# uC.net
KiCad netlist of a schematic drawn in Altium Designer
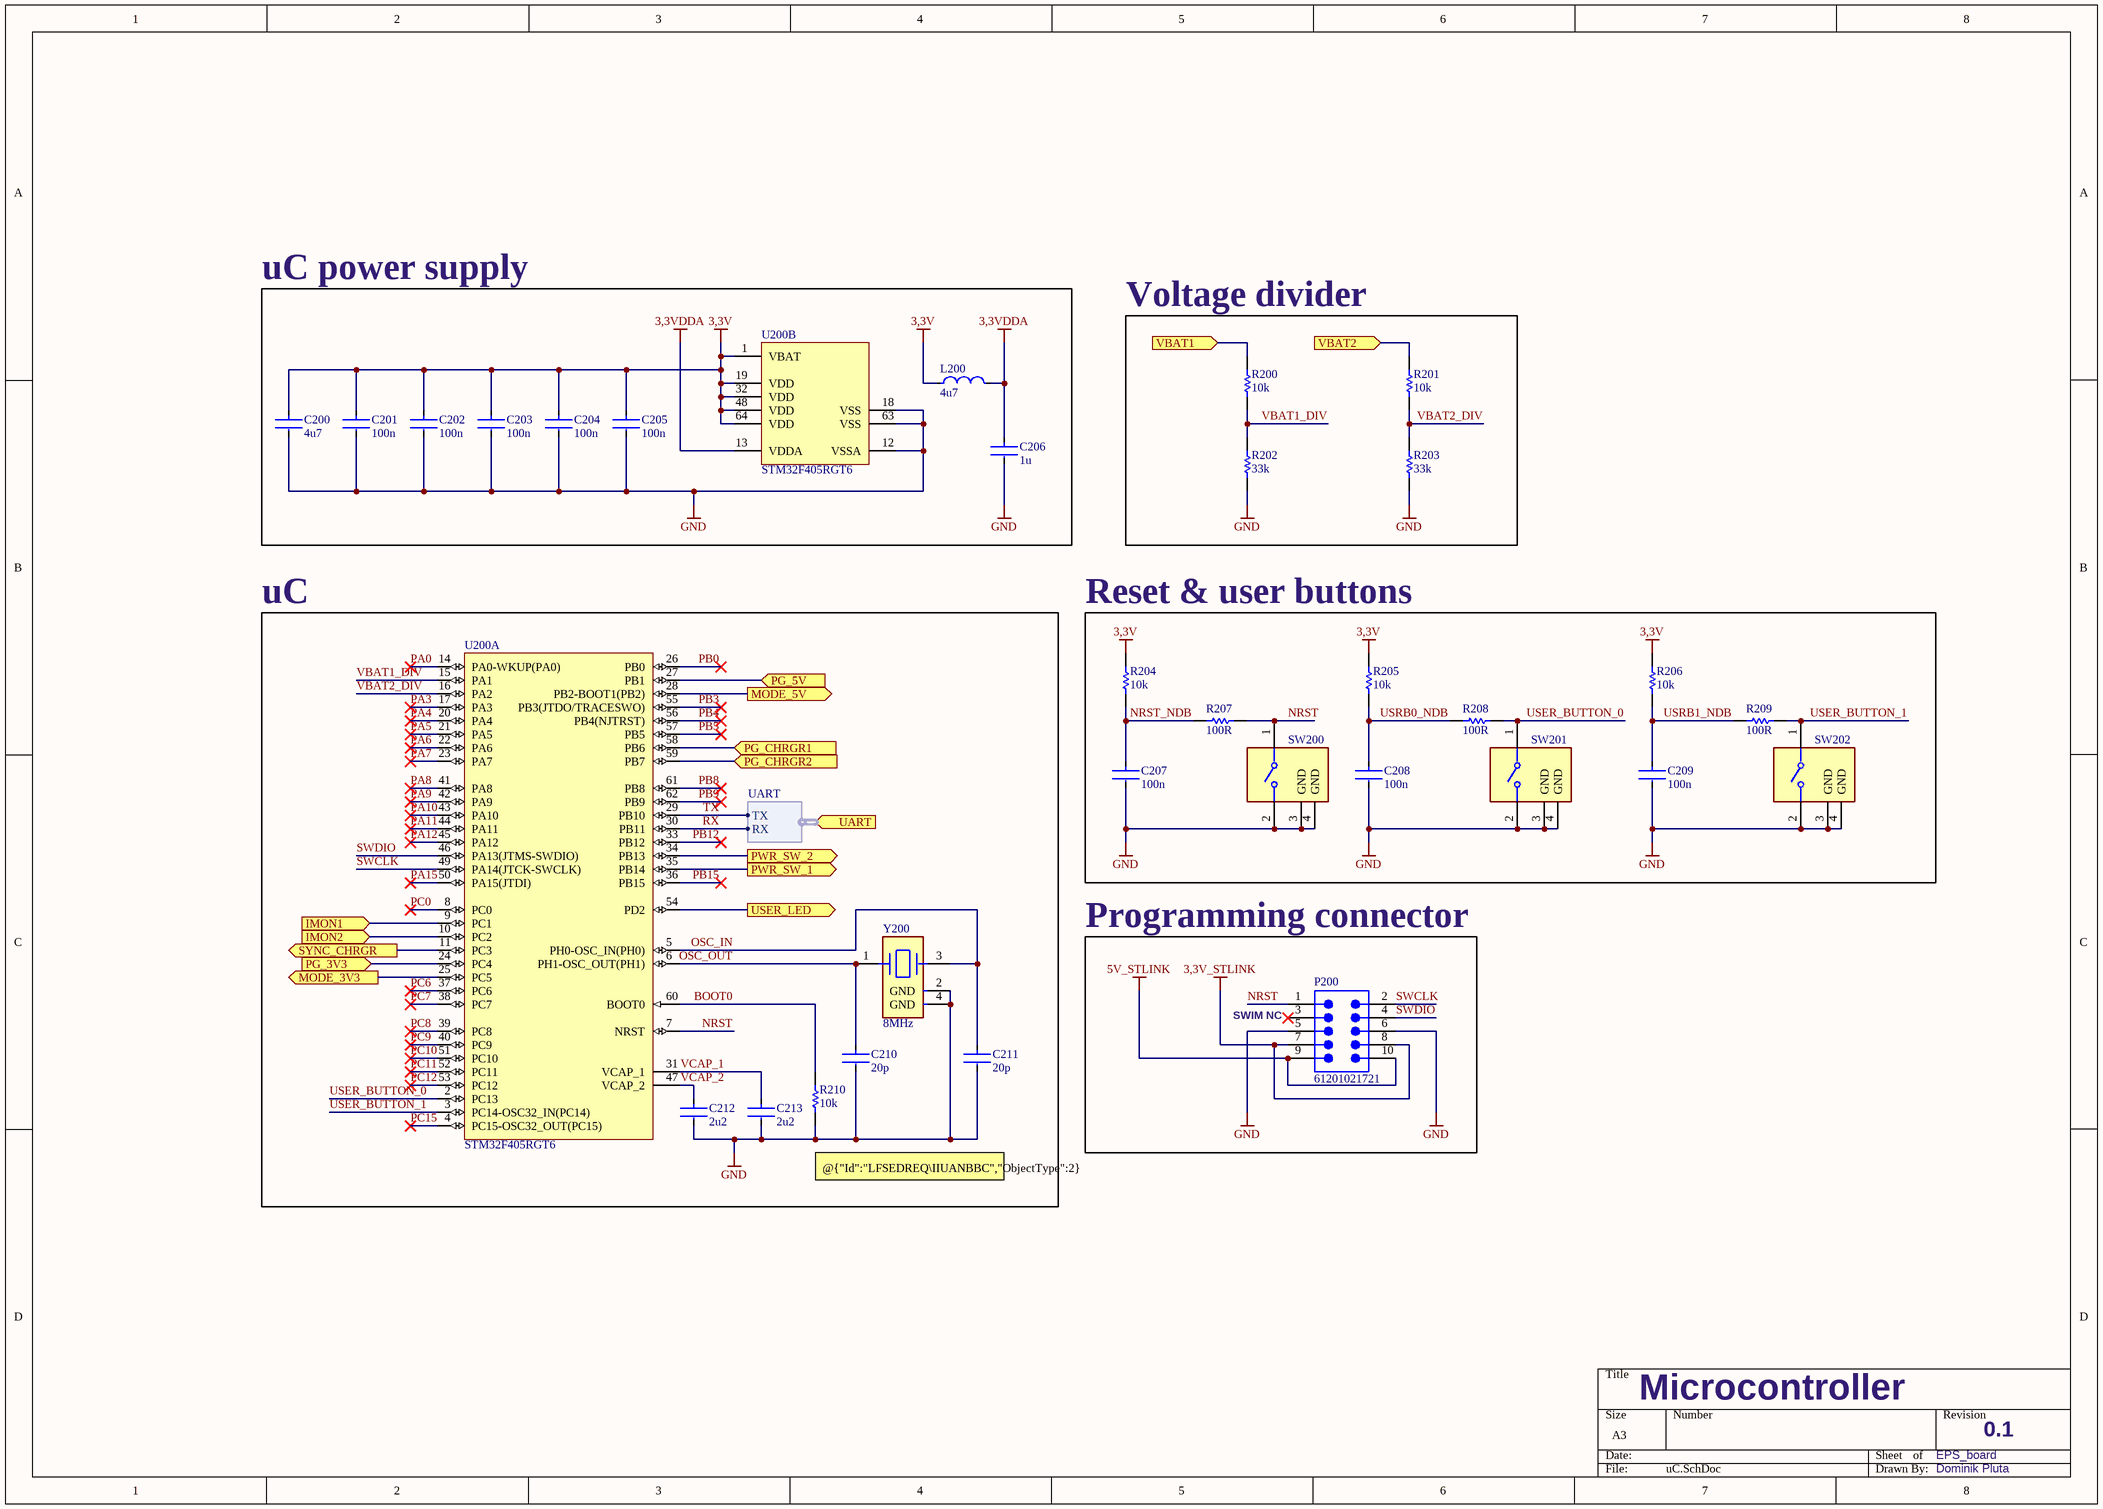
[diagram p0: uC.SchDoc]

(export (version "E")
  (design (tool "Eeschema 10.0.6"))
  (components
    (comp (ref "C200")
      (value "4u7")
      (footprint "FP-C0603C-CF-MFG")
      (description "CAP CER 0.1UF 50V X7R 0603")
      (fields (field (name "TOLERANCE") "0.1") (field (name "MANUFACTURER") "KEMET"))
      (libsource (lib "Altium Content Vault") (part "b4654b650e69147ec39a6b967a45e02"))
    )
    (comp (ref "C201")
      (value "100n")
      (footprint "FP-C0603C-CF-MFG")
      (description "CAP 0.1 μF, X5R or X7R ceramic")
      (fields (field (name "TOLERANCE") "10"))
      (libsource (lib "Altium Content Vault") (part "b4654b650e69147ec39a6b967a45e02"))
    )
    (comp (ref "C202")
      (value "100n")
      (footprint "FP-C0603C-CF-MFG")
      (description "CAP 0.1 μF, X5R or X7R ceramic")
      (fields (field (name "TOLERANCE") "10"))
      (libsource (lib "Altium Content Vault") (part "b4654b650e69147ec39a6b967a45e02"))
    )
    (comp (ref "C203")
      (value "100n")
      (footprint "FP-C0603C-CF-MFG")
      (description "CAP 0.1 μF, X5R or X7R ceramic")
      (fields (field (name "TOLERANCE") "10"))
      (libsource (lib "Altium Content Vault") (part "b4654b650e69147ec39a6b967a45e02"))
    )
    (comp (ref "C204")
      (value "100n")
      (footprint "FP-C0603C-CF-MFG")
      (description "CAP 0.1 μF, X5R or X7R ceramic")
      (fields (field (name "TOLERANCE") "10"))
      (libsource (lib "Altium Content Vault") (part "b4654b650e69147ec39a6b967a45e02"))
    )
    (comp (ref "C205")
      (value "100n")
      (footprint "FP-C0603C-CF-MFG")
      (description "CAP 0.1 μF, X5R or X7R ceramic")
      (fields (field (name "TOLERANCE") "10"))
      (libsource (lib "Altium Content Vault") (part "b4654b650e69147ec39a6b967a45e02"))
    )
    (comp (ref "C206")
      (value "1u")
      (footprint "FP-C0603C-CF-MFG")
      (description "CAP CER 0.1UF 50V X7R 0603")
      (fields (field (name "TOLERANCE") "0.1") (field (name "MANUFACTURER") "KEMET"))
      (libsource (lib "Altium Content Vault") (part "b4654b650e69147ec39a6b967a45e02"))
    )
    (comp (ref "C207")
      (value "100n")
      (footprint "FP-C0603C-CF-MFG")
      (description "CAP 0.1 μF, ceramic")
      (fields (field (name "TOLERANCE") "10"))
      (libsource (lib "Altium Content Vault") (part "b4654b650e69147ec39a6b967a45e02"))
    )
    (comp (ref "C208")
      (value "100n")
      (footprint "FP-C0603C-CF-MFG")
      (description "CAP 0.1 μF, ceramic")
      (fields (field (name "TOLERANCE") "10"))
      (libsource (lib "Altium Content Vault") (part "b4654b650e69147ec39a6b967a45e02"))
    )
    (comp (ref "C209")
      (value "100n")
      (footprint "FP-C0603C-CF-MFG")
      (description "CAP 0.1 μF, ceramic")
      (fields (field (name "TOLERANCE") "10"))
      (libsource (lib "Altium Content Vault") (part "b4654b650e69147ec39a6b967a45e02"))
    )
    (comp (ref "C210")
      (value "20p")
      (footprint "FP-C0603C-CF-MFG")
      (description "CAP CER 50V X7R 0603")
      (fields (field (name "TOLERANCE") "0.1") (field (name "MANUFACTURER") "KEMET"))
      (libsource (lib "Altium Content Vault") (part "b4654b650e69147ec39a6b967a45e02"))
    )
    (comp (ref "C211")
      (value "20p")
      (footprint "FP-C0603C-CF-MFG")
      (description "CAP CER 50V X7R 0603")
      (fields (field (name "TOLERANCE") "0.1") (field (name "MANUFACTURER") "KEMET"))
      (libsource (lib "Altium Content Vault") (part "b4654b650e69147ec39a6b967a45e02"))
    )
    (comp (ref "C212")
      (value "2u2")
      (footprint "FP-C0603C-CF-MFG")
      (description "CAP CER 50V X7R 0603")
      (fields (field (name "TOLERANCE") "0.1") (field (name "MANUFACTURER") "KEMET"))
      (libsource (lib "Altium Content Vault") (part "b4654b650e69147ec39a6b967a45e02"))
    )
    (comp (ref "C213")
      (value "2u2")
      (footprint "FP-C0603C-CF-MFG")
      (description "CAP CER 50V X7R 0603")
      (fields (field (name "TOLERANCE") "0.1") (field (name "MANUFACTURER") "KEMET"))
      (libsource (lib "Altium Content Vault") (part "b4654b650e69147ec39a6b967a45e02"))
    )
    (comp (ref "L200")
      (value "4u7")
      (footprint "FP-LQM21DN_00-MFG")
      (description "Multilayer Type Inductor for General Circuits, 0805 (2012), 0.22μH, 10%, 0.38Ω, 250mA")
      (fields (field (name "TOLERANCE") "10%"))
      (libsource (lib "Altium Content Vault") (part "725321dda6339637d4d059423bc1c3c"))
    )
    (comp (ref "P200")
      (value "61201021721")
      (footprint "61201021721")
      (libsource (lib "Altium Content Vault") (part "Header_Male_2R_10P"))
    )
    (comp (ref "R200")
      (value "10k")
      (footprint "RESC0603(1608)_N")
      (description "10k 0.1W 5% 0603 SMD")
      (fields (field (name "TOLERANCE") "5 %") (field (name "POWER") "0.1 W"))
      (libsource (lib "Altium Content Vault") (part "RES"))
    )
    (comp (ref "R201")
      (value "10k")
      (footprint "RESC0603(1608)_N")
      (description "10k 0.1W 5% 0603  SMD")
      (fields (field (name "TOLERANCE") "5 %") (field (name "POWER") "0.1 W"))
      (libsource (lib "Altium Content Vault") (part "RES"))
    )
    (comp (ref "R202")
      (value "33k")
      (footprint "RESC0603(1608)_N")
      (description "33k 0.1W 5% 0603 SMD")
      (fields (field (name "TOLERANCE") "5 %") (field (name "POWER") "0.1 W"))
      (libsource (lib "Altium Content Vault") (part "RES"))
    )
    (comp (ref "R203")
      (value "33k")
      (footprint "RESC0603(1608)_N")
      (description "33k 0.1W 5% 0603 SMD")
      (fields (field (name "TOLERANCE") "5 %") (field (name "POWER") "0.1 W"))
      (libsource (lib "Altium Content Vault") (part "RES"))
    )
    (comp (ref "R204")
      (value "10k")
      (footprint "RESC0603(1608)_N")
      (description "10k 0.1W 5% 0603 SMD")
      (fields (field (name "TOLERANCE") "5 %") (field (name "POWER") "0.1 W"))
      (libsource (lib "Altium Content Vault") (part "RES"))
    )
    (comp (ref "R205")
      (value "10k")
      (footprint "RESC0603(1608)_N")
      (description "10k 0.1W 5% 0603 SMD")
      (fields (field (name "TOLERANCE") "5 %") (field (name "POWER") "0.1 W"))
      (libsource (lib "Altium Content Vault") (part "RES"))
    )
    (comp (ref "R206")
      (value "10k")
      (footprint "RESC0603(1608)_N")
      (description "10k 0.1W 5% 0603 SMD")
      (fields (field (name "TOLERANCE") "5 %") (field (name "POWER") "0.1 W"))
      (libsource (lib "Altium Content Vault") (part "RES"))
    )
    (comp (ref "R207")
      (value "100R")
      (footprint "RESC0603(1608)_N")
      (description "100R 0.1W 5% 0603  SMD")
      (fields (field (name "TOLERANCE") "5 %") (field (name "POWER") "0.1 W"))
      (libsource (lib "Altium Content Vault") (part "RES"))
    )
    (comp (ref "R208")
      (value "100R")
      (footprint "RESC0603(1608)_N")
      (description "100R 0.1W 5% 0603  SMD")
      (fields (field (name "TOLERANCE") "5 %") (field (name "POWER") "0.1 W"))
      (libsource (lib "Altium Content Vault") (part "RES"))
    )
    (comp (ref "R209")
      (value "100R")
      (footprint "RESC0603(1608)_N")
      (description "100R 0.1W 5% 0603  SMD")
      (fields (field (name "TOLERANCE") "5 %") (field (name "POWER") "0.1 W"))
      (libsource (lib "Altium Content Vault") (part "RES"))
    )
    (comp (ref "R210")
      (value "10k")
      (footprint "RESC0603(1608)_N")
      (description "10k 0.1W 5% 0603 SMD")
      (fields (field (name "TOLERANCE") "5 %") (field (name "POWER") "0.1 W"))
      (libsource (lib "Altium Content Vault") (part "RES"))
    )
    (comp (ref "SW200")
      (value "B3F-3122")
      (footprint "FP-B3F-3122-MFG")
      (description "SWITCH TACTILE SPST-NO 0.05A 24V")
      (libsource (lib "Altium Content Vault") (part "05c531d4b500f7e9514fa3f65f375ae"))
    )
    (comp (ref "SW201")
      (value "B3F-3122")
      (footprint "FP-B3F-3122-MFG")
      (description "SWITCH TACTILE SPST-NO 0.05A 24V")
      (libsource (lib "Altium Content Vault") (part "05c531d4b500f7e9514fa3f65f375ae"))
    )
    (comp (ref "SW202")
      (value "B3F-3122")
      (footprint "FP-B3F-3122-MFG")
      (description "SWITCH TACTILE SPST-NO 0.05A 24V")
      (libsource (lib "Altium Content Vault") (part "05c531d4b500f7e9514fa3f65f375ae"))
    )
    (comp (ref "U200")
      (value "STM32F405RGT6")
      (footprint "STM-LQFP64_M")
      (fields (field (name "MANUFACTURER") "STMicroelectronics"))
      (libsource (lib "Altium Content Vault") (part "MC-ARM-STM32F4X5-SQ64"))
    )
    (comp (ref "Y200")
      (value "8MHz")
      (footprint "FP-7M-MFG")
      (description "Crystal oscillator 8MHz")
      (fields (field (name "TOLERANCE") "10ppm"))
      (libsource (lib "Altium Content Vault") (part "41079aabb0e87794b56622915be14ed"))
    )
  )
  (nets
    (net (code "3") (name "/BOOT0") (class "Default")
      (node (ref "R210") (pin "2") (pinfunction "2_2") (pintype "passive"))
      (node (ref "U200") (pin "60") (pinfunction "BOOT0_60") (pintype "input"))
    )
    (net (code "4") (name "/IMON1") (class "Default")
      (node (ref "U200") (pin "9") (pinfunction "PC1_9") (pintype "bidirectional"))
    )
    (net (code "5") (name "/IMON2") (class "Default")
      (node (ref "U200") (pin "10") (pinfunction "PC2_10") (pintype "bidirectional"))
    )
    (net (code "6") (name "/MODE_3V3") (class "Default")
      (node (ref "U200") (pin "25") (pinfunction "PC5_25") (pintype "bidirectional"))
    )
    (net (code "7") (name "/MODE_5V") (class "Default")
      (node (ref "U200") (pin "28") (pinfunction "PB2-BOOT1(PB2)_28") (pintype "bidirectional"))
    )
    (net (code "8") (name "/NRST") (class "Default")
      (node (ref "P200") (pin "1") (pinfunction "1_1") (pintype "passive"))
      (node (ref "R207") (pin "1") (pinfunction "1_1") (pintype "passive"))
      (node (ref "SW200") (pin "1") (pinfunction "1_1") (pintype "passive"))
      (node (ref "U200") (pin "7") (pinfunction "NRST_7") (pintype "bidirectional"))
    )
    (net (code "9") (name "/NRST_NDB") (class "Default")
      (node (ref "C207") (pin "1") (pinfunction "1_1") (pintype "passive"))
      (node (ref "R204") (pin "1") (pinfunction "1_1") (pintype "passive"))
      (node (ref "R207") (pin "2") (pinfunction "2_2") (pintype "passive"))
    )
    (net (code "10") (name "/OSC_IN") (class "Default")
      (node (ref "C211") (pin "1") (pinfunction "1_1") (pintype "passive"))
      (node (ref "U200") (pin "5") (pinfunction "PH0-OSC_IN(PH0)_5") (pintype "bidirectional"))
      (node (ref "Y200") (pin "3") (pinfunction "3_3") (pintype "passive"))
    )
    (net (code "11") (name "/OSC_OUT") (class "Default")
      (node (ref "C210") (pin "1") (pinfunction "1_1") (pintype "passive"))
      (node (ref "U200") (pin "6") (pinfunction "PH1-OSC_OUT(PH1)_6") (pintype "bidirectional"))
      (node (ref "Y200") (pin "1") (pinfunction "1_1") (pintype "passive"))
    )
    (net (code "12") (name "/PA0") (class "Default")
      (node (ref "U200") (pin "14") (pinfunction "PA0-WKUP(PA0)_14") (pintype "bidirectional+no_connect"))
    )
    (net (code "13") (name "/PA3") (class "Default")
      (node (ref "U200") (pin "17") (pinfunction "PA3_17") (pintype "bidirectional+no_connect"))
    )
    (net (code "14") (name "/PA4") (class "Default")
      (node (ref "U200") (pin "20") (pinfunction "PA4_20") (pintype "bidirectional+no_connect"))
    )
    (net (code "15") (name "/PA5") (class "Default")
      (node (ref "U200") (pin "21") (pinfunction "PA5_21") (pintype "bidirectional+no_connect"))
    )
    (net (code "16") (name "/PA6") (class "Default")
      (node (ref "U200") (pin "22") (pinfunction "PA6_22") (pintype "bidirectional+no_connect"))
    )
    (net (code "17") (name "/PA7") (class "Default")
      (node (ref "U200") (pin "23") (pinfunction "PA7_23") (pintype "bidirectional+no_connect"))
    )
    (net (code "18") (name "/PA8") (class "Default")
      (node (ref "U200") (pin "41") (pinfunction "PA8_41") (pintype "bidirectional+no_connect"))
    )
    (net (code "19") (name "/PA9") (class "Default")
      (node (ref "U200") (pin "42") (pinfunction "PA9_42") (pintype "bidirectional+no_connect"))
    )
    (net (code "20") (name "/PA10") (class "Default")
      (node (ref "U200") (pin "43") (pinfunction "PA10_43") (pintype "bidirectional+no_connect"))
    )
    (net (code "21") (name "/PA11") (class "Default")
      (node (ref "U200") (pin "44") (pinfunction "PA11_44") (pintype "bidirectional+no_connect"))
    )
    (net (code "22") (name "/PA12") (class "Default")
      (node (ref "U200") (pin "45") (pinfunction "PA12_45") (pintype "bidirectional+no_connect"))
    )
    (net (code "23") (name "/PA15") (class "Default")
      (node (ref "U200") (pin "50") (pinfunction "PA15(JTDI)_50") (pintype "bidirectional+no_connect"))
    )
    (net (code "24") (name "/PB0") (class "Default")
      (node (ref "U200") (pin "26") (pinfunction "PB0_26") (pintype "bidirectional+no_connect"))
    )
    (net (code "25") (name "/PB3") (class "Default")
      (node (ref "U200") (pin "55") (pinfunction "PB3(JTDO/TRACESWO)_55") (pintype "bidirectional+no_connect"))
    )
    (net (code "26") (name "/PB4") (class "Default")
      (node (ref "U200") (pin "56") (pinfunction "PB4(NJTRST)_56") (pintype "bidirectional+no_connect"))
    )
    (net (code "27") (name "/PB5") (class "Default")
      (node (ref "U200") (pin "57") (pinfunction "PB5_57") (pintype "bidirectional+no_connect"))
    )
    (net (code "28") (name "/PB8") (class "Default")
      (node (ref "U200") (pin "61") (pinfunction "PB8_61") (pintype "bidirectional+no_connect"))
    )
    (net (code "29") (name "/PB9") (class "Default")
      (node (ref "U200") (pin "62") (pinfunction "PB9_62") (pintype "bidirectional+no_connect"))
    )
    (net (code "30") (name "/PB12") (class "Default")
      (node (ref "U200") (pin "33") (pinfunction "PB12_33") (pintype "bidirectional+no_connect"))
    )
    (net (code "31") (name "/PB15") (class "Default")
      (node (ref "U200") (pin "36") (pinfunction "PB15_36") (pintype "bidirectional+no_connect"))
    )
    (net (code "32") (name "/PC0") (class "Default")
      (node (ref "U200") (pin "8") (pinfunction "PC0_8") (pintype "bidirectional+no_connect"))
    )
    (net (code "33") (name "/PC6") (class "Default")
      (node (ref "U200") (pin "37") (pinfunction "PC6_37") (pintype "bidirectional+no_connect"))
    )
    (net (code "34") (name "/PC7") (class "Default")
      (node (ref "U200") (pin "38") (pinfunction "PC7_38") (pintype "bidirectional+no_connect"))
    )
    (net (code "35") (name "/PC8") (class "Default")
      (node (ref "U200") (pin "39") (pinfunction "PC8_39") (pintype "bidirectional+no_connect"))
    )
    (net (code "36") (name "/PC9") (class "Default")
      (node (ref "U200") (pin "40") (pinfunction "PC9_40") (pintype "bidirectional+no_connect"))
    )
    (net (code "37") (name "/PC10") (class "Default")
      (node (ref "U200") (pin "51") (pinfunction "PC10_51") (pintype "bidirectional+no_connect"))
    )
    (net (code "38") (name "/PC11") (class "Default")
      (node (ref "U200") (pin "52") (pinfunction "PC11_52") (pintype "bidirectional+no_connect"))
    )
    (net (code "39") (name "/PC12") (class "Default")
      (node (ref "U200") (pin "53") (pinfunction "PC12_53") (pintype "bidirectional+no_connect"))
    )
    (net (code "40") (name "/PC15") (class "Default")
      (node (ref "U200") (pin "4") (pinfunction "PC15-OSC32_OUT(PC15)_4") (pintype "bidirectional+no_connect"))
    )
    (net (code "41") (name "/PG_3V3") (class "Default")
      (node (ref "U200") (pin "24") (pinfunction "PC4_24") (pintype "bidirectional"))
    )
    (net (code "42") (name "/PG_5V") (class "Default")
      (node (ref "U200") (pin "27") (pinfunction "PB1_27") (pintype "bidirectional"))
    )
    (net (code "43") (name "/PG_CHRGR1") (class "Default")
      (node (ref "U200") (pin "58") (pinfunction "PB6_58") (pintype "bidirectional"))
    )
    (net (code "44") (name "/PG_CHRGR2") (class "Default")
      (node (ref "U200") (pin "59") (pinfunction "PB7_59") (pintype "bidirectional"))
    )
    (net (code "45") (name "/PWR_SW_1") (class "Default")
      (node (ref "U200") (pin "35") (pinfunction "PB14_35") (pintype "bidirectional"))
    )
    (net (code "46") (name "/PWR_SW_2") (class "Default")
      (node (ref "U200") (pin "34") (pinfunction "PB13_34") (pintype "bidirectional"))
    )
    (net (code "47") (name "/RX") (class "Default")
      (node (ref "U200") (pin "30") (pinfunction "PB11_30") (pintype "bidirectional"))
    )
    (net (code "48") (name "/SWCLK") (class "Default")
      (node (ref "P200") (pin "2") (pinfunction "2_2") (pintype "passive"))
      (node (ref "U200") (pin "49") (pinfunction "PA14(JTCK-SWCLK)_49") (pintype "bidirectional"))
    )
    (net (code "49") (name "/SWDIO") (class "Default")
      (node (ref "P200") (pin "4") (pinfunction "4_4") (pintype "passive"))
      (node (ref "U200") (pin "46") (pinfunction "PA13(JTMS-SWDIO)_46") (pintype "bidirectional"))
    )
    (net (code "50") (name "/SYNC_CHRGR") (class "Default")
      (node (ref "U200") (pin "11") (pinfunction "PC3_11") (pintype "bidirectional"))
    )
    (net (code "51") (name "/TX") (class "Default")
      (node (ref "U200") (pin "29") (pinfunction "PB10_29") (pintype "bidirectional"))
    )
    (net (code "52") (name "/USER_BUTTON_0") (class "Default")
      (node (ref "R208") (pin "1") (pinfunction "1_1") (pintype "passive"))
      (node (ref "SW201") (pin "1") (pinfunction "1_1") (pintype "passive"))
      (node (ref "U200") (pin "2") (pinfunction "PC13_2") (pintype "bidirectional"))
    )
    (net (code "53") (name "/USER_BUTTON_1") (class "Default")
      (node (ref "R209") (pin "1") (pinfunction "1_1") (pintype "passive"))
      (node (ref "SW202") (pin "1") (pinfunction "1_1") (pintype "passive"))
      (node (ref "U200") (pin "3") (pinfunction "PC14-OSC32_IN(PC14)_3") (pintype "bidirectional"))
    )
    (net (code "54") (name "/USER_LED") (class "Default")
      (node (ref "U200") (pin "54") (pinfunction "PD2_54") (pintype "bidirectional"))
    )
    (net (code "55") (name "/USRB0_NDB") (class "Default")
      (node (ref "C208") (pin "1") (pinfunction "1_1") (pintype "passive"))
      (node (ref "R205") (pin "1") (pinfunction "1_1") (pintype "passive"))
      (node (ref "R208") (pin "2") (pinfunction "2_2") (pintype "passive"))
    )
    (net (code "56") (name "/USRB1_NDB") (class "Default")
      (node (ref "C209") (pin "1") (pinfunction "1_1") (pintype "passive"))
      (node (ref "R206") (pin "1") (pinfunction "1_1") (pintype "passive"))
      (node (ref "R209") (pin "2") (pinfunction "2_2") (pintype "passive"))
    )
    (net (code "57") (name "/VBAT1") (class "Default")
      (node (ref "R200") (pin "2") (pinfunction "2_2") (pintype "passive"))
    )
    (net (code "58") (name "/VBAT1_DIV") (class "Default")
      (node (ref "R200") (pin "1") (pinfunction "1_1") (pintype "passive"))
      (node (ref "R202") (pin "2") (pinfunction "2_2") (pintype "passive"))
      (node (ref "U200") (pin "15") (pinfunction "PA1_15") (pintype "bidirectional"))
    )
    (net (code "59") (name "/VBAT2") (class "Default")
      (node (ref "R201") (pin "2") (pinfunction "2_2") (pintype "passive"))
    )
    (net (code "60") (name "/VBAT2_DIV") (class "Default")
      (node (ref "R201") (pin "1") (pinfunction "1_1") (pintype "passive"))
      (node (ref "R203") (pin "2") (pinfunction "2_2") (pintype "passive"))
      (node (ref "U200") (pin "16") (pinfunction "PA2_16") (pintype "bidirectional"))
    )
    (net (code "61") (name "/VCAP_1") (class "Default")
      (node (ref "C213") (pin "1") (pinfunction "1_1") (pintype "passive"))
      (node (ref "U200") (pin "31") (pinfunction "VCAP_1_31") (pintype "power_in"))
    )
    (net (code "62") (name "/VCAP_2") (class "Default")
      (node (ref "C212") (pin "1") (pinfunction "1_1") (pintype "passive"))
      (node (ref "U200") (pin "47") (pinfunction "VCAP_2_47") (pintype "power_in"))
    )
    (net (code "64") (name "3,3V") (class "Default")
      (node (ref "C200") (pin "1") (pinfunction "1_1") (pintype "passive"))
      (node (ref "C201") (pin "1") (pinfunction "1_1") (pintype "passive"))
      (node (ref "C202") (pin "1") (pinfunction "1_1") (pintype "passive"))
      (node (ref "C203") (pin "1") (pinfunction "1_1") (pintype "passive"))
      (node (ref "C204") (pin "1") (pinfunction "1_1") (pintype "passive"))
      (node (ref "C205") (pin "1") (pinfunction "1_1") (pintype "passive"))
      (node (ref "L200") (pin "1") (pinfunction "1_1") (pintype "passive"))
      (node (ref "R204") (pin "2") (pinfunction "2_2") (pintype "passive"))
      (node (ref "R205") (pin "2") (pinfunction "2_2") (pintype "passive"))
      (node (ref "R206") (pin "2") (pinfunction "2_2") (pintype "passive"))
      (node (ref "U200") (pin "1") (pinfunction "VBAT_1") (pintype "power_in"))
      (node (ref "U200") (pin "19") (pinfunction "VDD_19") (pintype "power_in"))
      (node (ref "U200") (pin "32") (pinfunction "VDD_32") (pintype "power_in"))
      (node (ref "U200") (pin "48") (pinfunction "VDD_48") (pintype "power_in"))
      (node (ref "U200") (pin "64") (pinfunction "VDD_64") (pintype "power_in"))
    )
    (net (code "65") (name "3,3VDDA") (class "Default")
      (node (ref "C206") (pin "1") (pinfunction "1_1") (pintype "passive"))
      (node (ref "L200") (pin "2") (pinfunction "2_2") (pintype "passive"))
      (node (ref "U200") (pin "13") (pinfunction "VDDA_13") (pintype "power_in"))
    )
    (net (code "66") (name "3,3V_STLINK") (class "Default")
      (node (ref "P200") (pin "7") (pinfunction "7_7") (pintype "passive"))
      (node (ref "P200") (pin "8") (pinfunction "8_8") (pintype "passive"))
    )
    (net (code "67") (name "5V_STLINK") (class "Default")
      (node (ref "P200") (pin "10") (pinfunction "10_10") (pintype "passive"))
      (node (ref "P200") (pin "9") (pinfunction "9_9") (pintype "passive"))
    )
    (net (code "68") (name "GND") (class "Default")
      (node (ref "C200") (pin "2") (pinfunction "2_2") (pintype "passive"))
      (node (ref "C201") (pin "2") (pinfunction "2_2") (pintype "passive"))
      (node (ref "C202") (pin "2") (pinfunction "2_2") (pintype "passive"))
      (node (ref "C203") (pin "2") (pinfunction "2_2") (pintype "passive"))
      (node (ref "C204") (pin "2") (pinfunction "2_2") (pintype "passive"))
      (node (ref "C205") (pin "2") (pinfunction "2_2") (pintype "passive"))
      (node (ref "C206") (pin "2") (pinfunction "2_2") (pintype "passive"))
      (node (ref "C207") (pin "2") (pinfunction "2_2") (pintype "passive"))
      (node (ref "C208") (pin "2") (pinfunction "2_2") (pintype "passive"))
      (node (ref "C209") (pin "2") (pinfunction "2_2") (pintype "passive"))
      (node (ref "C210") (pin "2") (pinfunction "2_2") (pintype "passive"))
      (node (ref "C211") (pin "2") (pinfunction "2_2") (pintype "passive"))
      (node (ref "C212") (pin "2") (pinfunction "2_2") (pintype "passive"))
      (node (ref "C213") (pin "2") (pinfunction "2_2") (pintype "passive"))
      (node (ref "P200") (pin "5") (pinfunction "5_5") (pintype "passive"))
      (node (ref "P200") (pin "6") (pinfunction "6_6") (pintype "passive"))
      (node (ref "R202") (pin "1") (pinfunction "1_1") (pintype "passive"))
      (node (ref "R203") (pin "1") (pinfunction "1_1") (pintype "passive"))
      (node (ref "R210") (pin "1") (pinfunction "1_1") (pintype "passive"))
      (node (ref "SW200") (pin "2") (pinfunction "2_2") (pintype "passive"))
      (node (ref "SW200") (pin "3") (pinfunction "GND_3") (pintype "power_in"))
      (node (ref "SW200") (pin "4") (pinfunction "GND_4") (pintype "power_in"))
      (node (ref "SW201") (pin "2") (pinfunction "2_2") (pintype "passive"))
      (node (ref "SW201") (pin "3") (pinfunction "GND_3") (pintype "power_in"))
      (node (ref "SW201") (pin "4") (pinfunction "GND_4") (pintype "power_in"))
      (node (ref "SW202") (pin "2") (pinfunction "2_2") (pintype "passive"))
      (node (ref "SW202") (pin "3") (pinfunction "GND_3") (pintype "power_in"))
      (node (ref "SW202") (pin "4") (pinfunction "GND_4") (pintype "power_in"))
      (node (ref "U200") (pin "12") (pinfunction "VSSA_12") (pintype "power_in"))
      (node (ref "U200") (pin "18") (pinfunction "VSS_18") (pintype "power_in"))
      (node (ref "U200") (pin "63") (pinfunction "VSS_63") (pintype "power_in"))
      (node (ref "Y200") (pin "2") (pinfunction "GND_2") (pintype "power_in"))
      (node (ref "Y200") (pin "4") (pinfunction "GND_4") (pintype "power_in"))
    )
    (net (code "69") (name "unconnected-(P200-Pad3)") (class "Default")
      (node (ref "P200") (pin "3") (pinfunction "3_3") (pintype "passive+no_connect"))
    )
  )
)
